# Charger_18V-1_35A.net
KiCad netlist of a schematic drawn in EAGLE
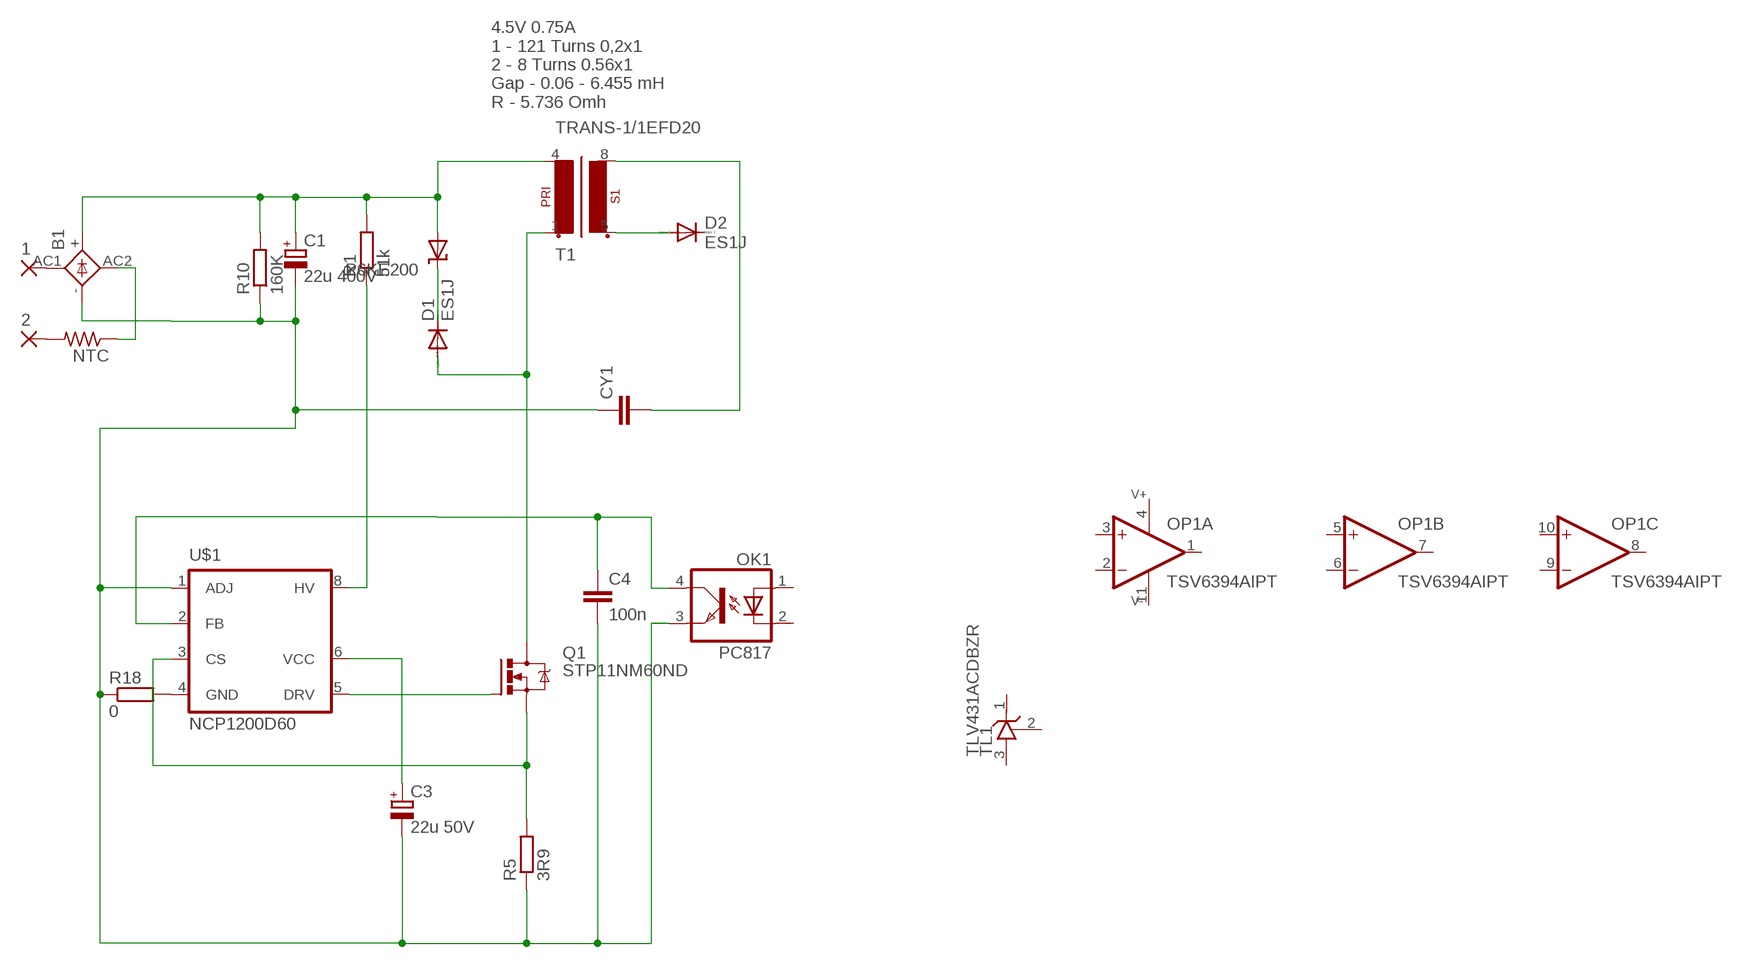
[diagram p0: schematic, sheet 1]

(export (version "E")
  (design (tool "Eeschema 10.0.6"))
  (components
    (comp (ref "1")
      (value "3,81/1,4")
      (footprint "eagle-import:3,81_1,4")
      (libsource (lib "eagle-import") (part "3,81/1,4"))
    )
    (comp (ref "2")
      (value "3,81/1,4")
      (footprint "eagle-import:3,81_1,4")
      (libsource (lib "eagle-import") (part "3,81/1,4"))
    )
    (comp (ref "B1")
      (value "BRIDGEDBS")
      (footprint "eagle-import:DBS")
      (libsource (lib "eagle-import") (part "BRIDGEDBS"))
    )
    (comp (ref "C1")
      (value "22u 400V")
      (footprint "eagle-import:E7,5-18")
      (libsource (lib "eagle-import") (part "CPOL-EUE7.5-18"))
    )
    (comp (ref "C3")
      (value "22u 50V")
      (footprint "eagle-import:E5-5")
      (libsource (lib "eagle-import") (part "CPOL-EUE5-5"))
    )
    (comp (ref "C4")
      (value "100n")
      (footprint "eagle-import:C0805")
      (libsource (lib "eagle-import") (part "C-EUC0805"))
    )
    (comp (ref "CY1")
      (value "CYYC10B4")
      (footprint "eagle-import:YC10B4")
      (libsource (lib "eagle-import") (part "CYYC10B4"))
    )
    (comp (ref "D1")
      (value "ES1J")
      (footprint "eagle-import:DO-214AC")
      (libsource (lib "eagle-import") (part "DIODE-DO-214AC"))
    )
    (comp (ref "D2")
      (value "ES1J")
      (footprint "eagle-import:DO-214AC")
      (libsource (lib "eagle-import") (part "DIODE-DO-214AC"))
    )
    (comp (ref "NTC")
      (value "R-US_0207/7")
      (footprint "eagle-import:0207_7")
      (libsource (lib "eagle-import") (part "R-US_0207/7"))
    )
    (comp (ref "OK1")
      (value "PC817")
      (footprint "eagle-import:DIL04")
      (fields (field (name "MPN") "PC817X4J000F"))
      (libsource (lib "eagle-import") (part "PC817"))
    )
    (comp (ref "OP1")
      (value "TSV6394AIPT")
      (footprint "eagle-import:TSSOP14")
      (libsource (lib "eagle-import") (part "OP-AMP-4LMV324IPT"))
    )
    (comp (ref "P6KE200")
      (value "SUPRESSORDO-204AC")
      (footprint "eagle-import:DO15-12")
      (libsource (lib "eagle-import") (part "SUPRESSORDO-204AC"))
    )
    (comp (ref "Q1")
      (value "STP11NM60ND")
      (footprint "eagle-import:TO220BV")
      (libsource (lib "eagle-import") (part "IRF740"))
    )
    (comp (ref "R1")
      (value "51k")
      (footprint "eagle-import:SQP-5")
      (libsource (lib "eagle-import") (part "R_SQP-5"))
    )
    (comp (ref "R5")
      (value "3R9")
      (footprint "eagle-import:0309_12")
      (libsource (lib "eagle-import") (part "R-EU_0309/12"))
    )
    (comp (ref "R10")
      (value "160K")
      (footprint "eagle-import:0204_7")
      (libsource (lib "eagle-import") (part "R-EU_0204/7"))
    )
    (comp (ref "R18")
      (value "0")
      (footprint "eagle-import:R1206")
      (libsource (lib "eagle-import") (part "R-EU_R1206"))
    )
    (comp (ref "T1")
      (value "TRANS-1/1EFD20")
      (footprint "eagle-import:EFD20_8PIN")
      (libsource (lib "eagle-import") (part "TRANS-1/1EFD20"))
    )
    (comp (ref "TL1")
      (value "TLV431ACDBZR")
      (footprint "eagle-import:SOT23")
      (libsource (lib "eagle-import") (part "IC-TL431CDBZR"))
    )
    (comp (ref "U$1")
      (value "NCP1200D60")
      (footprint "eagle-import:DIP08")
      (libsource (lib "eagle-import") (part "NCP1200-100DIL"))
    )
  )
  (nets
    (net (code "1") (name "/V+") (class "Default")
      (node (ref "OP1") (pin "4") (pinfunction "V+_4") (pintype "power_in"))
    )
    (net (code "2") (name "/V-") (class "Default")
      (node (ref "OP1") (pin "11") (pinfunction "V-_11") (pintype "power_in"))
    )
    (net (code "3") (name "Net-(1-P)") (class "Default")
      (node (ref "1") (pin "1") (pinfunction "P_1") (pintype "passive"))
      (node (ref "B1") (pin "AC1") (pinfunction "AC1_AC1") (pintype "passive"))
    )
    (net (code "4") (name "Net-(2-P)") (class "Default")
      (node (ref "2") (pin "1") (pinfunction "P_1") (pintype "passive"))
      (node (ref "NTC") (pin "2") (pinfunction "2_2") (pintype "passive"))
    )
    (net (code "5") (name "Net-(B1-PadAC2)") (class "Default")
      (node (ref "B1") (pin "AC2") (pinfunction "AC2_AC2") (pintype "passive"))
      (node (ref "NTC") (pin "1") (pinfunction "1_1") (pintype "passive"))
    )
    (net (code "6") (name "Net-(D1-PadC)") (class "Default")
      (node (ref "D1") (pin "C") (pinfunction "C_C") (pintype "passive"))
      (node (ref "P6KE200") (pin "C") (pinfunction "C_C") (pintype "passive"))
    )
    (net (code "7") (name "Net-(OK1-COL)") (class "Default")
      (node (ref "C4") (pin "1") (pinfunction "1_1") (pintype "passive"))
      (node (ref "OK1") (pin "4") (pinfunction "COL_4") (pintype "passive"))
      (node (ref "U$1") (pin "2") (pinfunction "FB_2") (pintype "input"))
    )
    (net (code "8") (name "Net-(OK1-EMIT)") (class "Default")
      (node (ref "B1") (pin "-") (pinfunction "-_-") (pintype "passive"))
      (node (ref "C1") (pin "-") (pinfunction "-_-") (pintype "passive"))
      (node (ref "C3") (pin "-") (pinfunction "-_-") (pintype "passive"))
      (node (ref "C4") (pin "2") (pinfunction "2_2") (pintype "passive"))
      (node (ref "CY1") (pin "1") (pinfunction "1_1") (pintype "passive"))
      (node (ref "OK1") (pin "3") (pinfunction "EMIT_3") (pintype "passive"))
      (node (ref "R10") (pin "1") (pinfunction "1_1") (pintype "passive"))
      (node (ref "R18") (pin "1") (pinfunction "1_1") (pintype "passive"))
      (node (ref "R5") (pin "1") (pinfunction "1_1") (pintype "passive"))
      (node (ref "U$1") (pin "1") (pinfunction "ADJ_1") (pintype "passive"))
    )
    (net (code "9") (name "Net-(T1-P1-1)") (class "Default")
      (node (ref "D1") (pin "A") (pinfunction "A_A") (pintype "passive"))
      (node (ref "Q1") (pin "D") (pinfunction "D_D") (pintype "passive"))
      (node (ref "T1") (pin "1") (pinfunction "P1-1_1") (pintype "passive"))
    )
    (net (code "10") (name "Net-(T1-P1-2)") (class "Default")
      (node (ref "B1") (pin "+") (pinfunction "+_+") (pintype "passive"))
      (node (ref "C1") (pin "+") (pinfunction "+_+") (pintype "passive"))
      (node (ref "P6KE200") (pin "A") (pinfunction "A_A") (pintype "passive"))
      (node (ref "R1") (pin "2") (pinfunction "2_2") (pintype "passive"))
      (node (ref "R10") (pin "2") (pinfunction "2_2") (pintype "passive"))
      (node (ref "T1") (pin "4") (pinfunction "P1-2_4") (pintype "passive"))
    )
    (net (code "11") (name "Net-(T1-S1-1)") (class "Default")
      (node (ref "D2") (pin "A") (pinfunction "A_A") (pintype "passive"))
      (node (ref "T1") (pin "5") (pinfunction "S1-1_5") (pintype "passive"))
    )
    (net (code "12") (name "Net-(T1-S1-2)") (class "Default")
      (node (ref "CY1") (pin "2") (pinfunction "2_2") (pintype "passive"))
      (node (ref "T1") (pin "8") (pinfunction "S1-2_8") (pintype "passive"))
    )
    (net (code "13") (name "Net-(U$1-CS)") (class "Default")
      (node (ref "Q1") (pin "S") (pinfunction "S_S") (pintype "passive"))
      (node (ref "R5") (pin "2") (pinfunction "2_2") (pintype "passive"))
      (node (ref "U$1") (pin "3") (pinfunction "CS_3") (pintype "input"))
    )
    (net (code "14") (name "Net-(U$1-DRV)") (class "Default")
      (node (ref "Q1") (pin "G") (pinfunction "G_G") (pintype "passive"))
      (node (ref "U$1") (pin "5") (pinfunction "DRV_5") (pintype "power_in"))
    )
    (net (code "15") (name "Net-(U$1-GND)") (class "Default")
      (node (ref "R18") (pin "2") (pinfunction "2_2") (pintype "passive"))
      (node (ref "U$1") (pin "4") (pinfunction "GND_4") (pintype "passive"))
    )
    (net (code "16") (name "Net-(U$1-HV)") (class "Default")
      (node (ref "R1") (pin "1") (pinfunction "1_1") (pintype "passive"))
      (node (ref "U$1") (pin "8") (pinfunction "HV_8") (pintype "passive"))
    )
    (net (code "17") (name "Net-(U$1-VCC)") (class "Default")
      (node (ref "C3") (pin "+") (pinfunction "+_+") (pintype "passive"))
      (node (ref "U$1") (pin "6") (pinfunction "VCC_6") (pintype "output"))
    )
    (net (code "18") (name "unconnected-(D2-PadC)") (class "Default")
      (node (ref "D2") (pin "C") (pinfunction "C_C") (pintype "passive"))
    )
    (net (code "19") (name "unconnected-(OK1-A-Pad1)") (class "Default")
      (node (ref "OK1") (pin "1") (pinfunction "A_1") (pintype "passive"))
    )
    (net (code "20") (name "unconnected-(OK1-C-Pad2)") (class "Default")
      (node (ref "OK1") (pin "2") (pinfunction "C_2") (pintype "passive"))
    )
    (net (code "21") (name "unconnected-(OP1A-+IN-Pad3)") (class "Default")
      (node (ref "OP1") (pin "3") (pinfunction "+IN_3") (pintype "input"))
    )
    (net (code "22") (name "unconnected-(OP1A--IN-Pad2)") (class "Default")
      (node (ref "OP1") (pin "2") (pinfunction "-IN_2") (pintype "input"))
    )
    (net (code "23") (name "unconnected-(OP1A-OUT-Pad1)") (class "Default")
      (node (ref "OP1") (pin "1") (pinfunction "OUT_1") (pintype "output"))
    )
    (net (code "24") (name "unconnected-(OP1B-+IN-Pad5)") (class "Default")
      (node (ref "OP1") (pin "5") (pinfunction "+IN_5") (pintype "input"))
    )
    (net (code "25") (name "unconnected-(OP1B--IN-Pad6)") (class "Default")
      (node (ref "OP1") (pin "6") (pinfunction "-IN_6") (pintype "input"))
    )
    (net (code "26") (name "unconnected-(OP1B-OUT-Pad7)") (class "Default")
      (node (ref "OP1") (pin "7") (pinfunction "OUT_7") (pintype "output"))
    )
    (net (code "27") (name "unconnected-(OP1C-+IN-Pad10)") (class "Default")
      (node (ref "OP1") (pin "10") (pinfunction "+IN_10") (pintype "input"))
    )
    (net (code "28") (name "unconnected-(OP1C--IN-Pad9)") (class "Default")
      (node (ref "OP1") (pin "9") (pinfunction "-IN_9") (pintype "input"))
    )
    (net (code "29") (name "unconnected-(OP1C-OUT-Pad8)") (class "Default")
      (node (ref "OP1") (pin "8") (pinfunction "OUT_8") (pintype "output"))
    )
    (net (code "30") (name "unconnected-(TL1-A-Pad3)") (class "Default")
      (node (ref "TL1") (pin "3") (pinfunction "A_3") (pintype "passive"))
    )
    (net (code "31") (name "unconnected-(TL1-C-Pad1)") (class "Default")
      (node (ref "TL1") (pin "1") (pinfunction "C_1") (pintype "passive"))
    )
    (net (code "32") (name "unconnected-(TL1-R-Pad2)") (class "Default")
      (node (ref "TL1") (pin "2") (pinfunction "R_2") (pintype "passive"))
    )
  )
)
